# 06_USB_Interface.net
KiCad netlist of a schematic drawn in Altium Designer
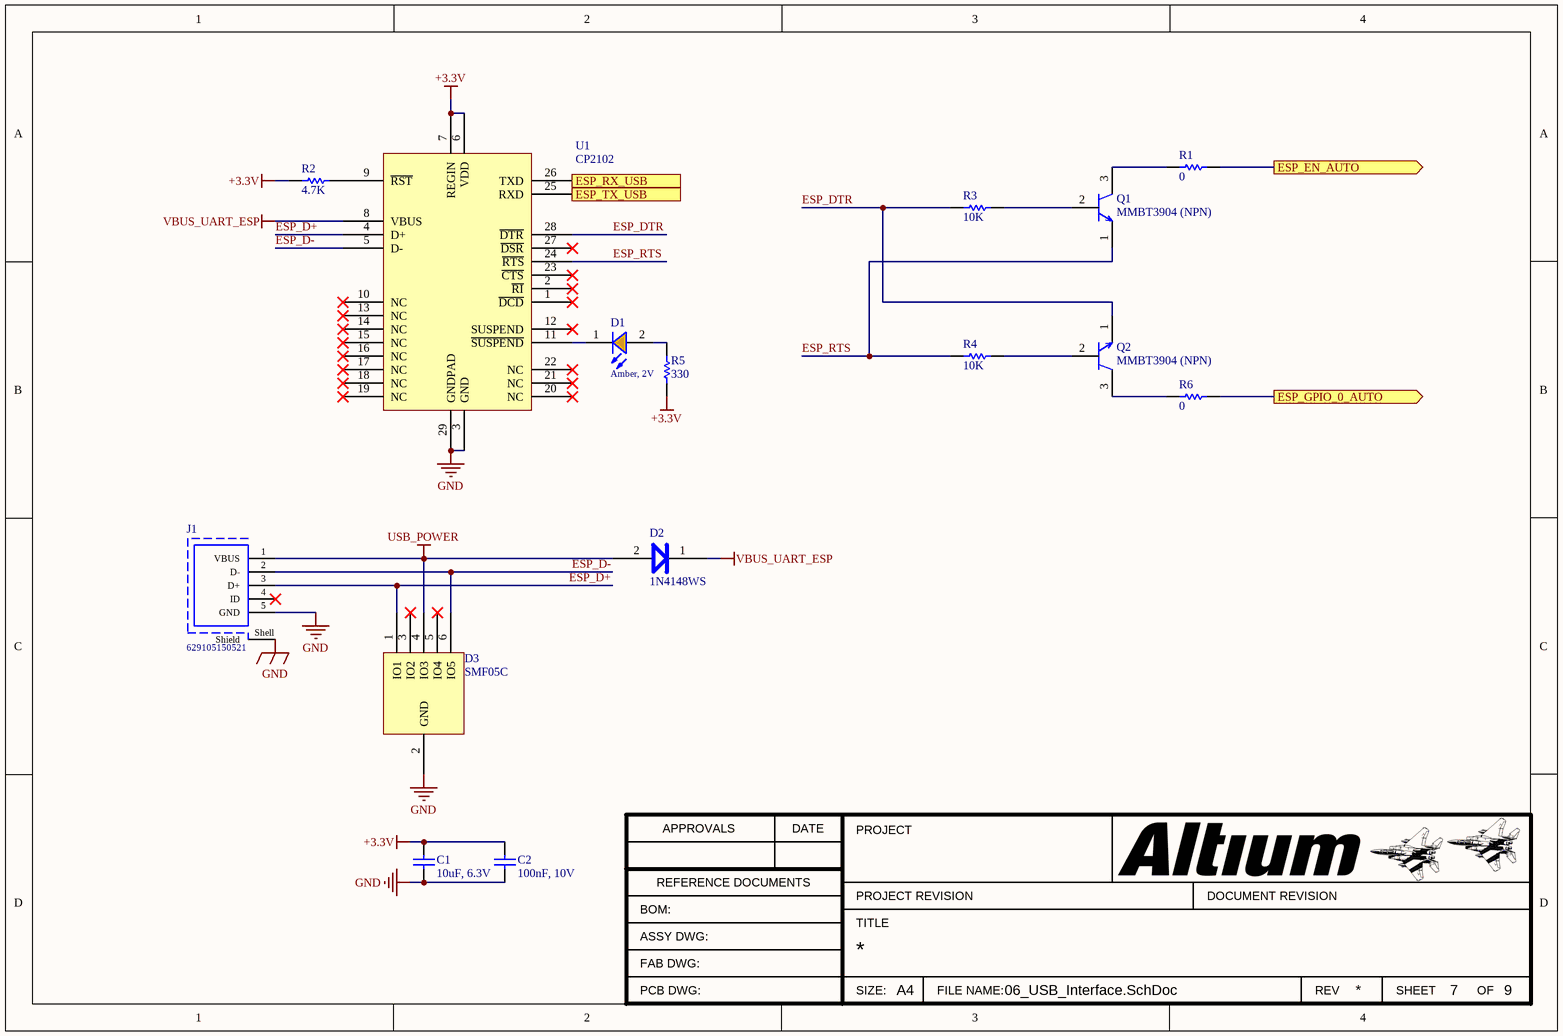
[diagram p0: 06_USB_Interface.SchDoc]

(export (version "E")
  (design (tool "Eeschema 10.0.6"))
  (components
    (comp (ref "C1")
      (value "10uF, 6.3V")
      (footprint "WCAP-CSGP_0603_H=0.8mm_Reflow")
      (description "WCAP-CSGP Multilayer Ceramic Chip Capacitor, General Purpose, size 0603, X5R, 10uF, 6.3V")
      (fields
        (field (name "MANUFACTURER PART NUMBER") "885012106006")
        (field (name "MANUFACTURER") "Wurth Elektronik")
      )
      (libsource (lib "Altium_WCAP-CSGP (rev20a)") (part "885012106006"))
    )
    (comp (ref "C2")
      (value "100nF, 10V")
      (footprint "WCAP-CSGP_0603_H=0.8mm_Reflow")
      (description "WCAP-CSGP Multilayer Ceramic Chip Capacitor, General Purpose, size 0603, X7R, 100nF, 10V")
      (fields
        (field (name "MANUFACTURER PART NUMBER") "885012206020")
        (field (name "MANUFACTURER") "Wurth Elektronik")
      )
      (libsource (lib "Altium_WCAP-CSGP (rev20a)") (part "885012206020"))
    )
    (comp (ref "D1")
      (value "Amber, 2V")
      (footprint "WL-SMCW_0603_H=0.7mm")
      (description "WL-SMCW SMT Mono-color Chip LED Waterclear, size 0603, Amber, 2V, 140deg")
      (fields (field (name "PART NUMBER") "150060AS75000") (field (name "PUBLISHER") "Wurth Elektronik"))
      (libsource (lib "Altium_WL-SMCW (rev20a)") (part "150060AS75000"))
    )
    (comp (ref "D2")
      (value "1N4148WS")
      (footprint "SODFL250X90-2N")
      (libsource (lib "MiclsLib") (part "1N4148WS"))
    )
    (comp (ref "D3")
      (value "SMF05C")
      (footprint "SOT65P210X110-6N")
      (libsource (lib "MiclsLib") (part "SMF05C"))
    )
    (comp (ref "J1")
      (value "629105150521")
      (footprint "629105150521")
      (description "Micro USB 2.0 Type B Receptacle WR-COM, Horizontal, SMT, with Pegs, High Current at Pin 1 & Pin 5")
      (fields (field (name "PUBLISHER") "Wurth Elektronik"))
      (libsource (lib "ALTIUM-WR-COM_USB_20-rev18d") (part "629105150521"))
    )
    (comp (ref "Q1")
      (value "MMBT3904 (NPN)")
      (footprint "SOT95P245X110-3N")
      (fields (field (name "MANUFACTURER") "On Semiconductor"))
      (libsource (lib "MiclsLib") (part "MMBT3904 (NPN)"))
    )
    (comp (ref "Q2")
      (value "MMBT3904 (NPN)")
      (footprint "SOT95P245X110-3N")
      (fields (field (name "MANUFACTURER") "On Semiconductor"))
      (libsource (lib "MiclsLib") (part "MMBT3904 (NPN)"))
    )
    (comp (ref "R1")
      (value "0")
      (footprint "RES-SM-0603")
      (description "Resistor")
      (fields (field (name "Comment") "RESISTOR SMD"))
      (libsource (lib "PIF_Library") (part "RESISTOR SMD"))
    )
    (comp (ref "R2")
      (value "4.7K")
      (footprint "RES-SM-0603")
      (description "Resistor")
      (fields (field (name "Comment") "RESISTOR SMD"))
      (libsource (lib "PIF_Library") (part "RESISTOR SMD"))
    )
    (comp (ref "R3")
      (value "10K")
      (footprint "RES-SM-0603")
      (description "Resistor")
      (fields (field (name "Comment") "RESISTOR SMD"))
      (libsource (lib "PIF_Library") (part "RESISTOR SMD"))
    )
    (comp (ref "R4")
      (value "10K")
      (footprint "RES-SM-0603")
      (description "Resistor")
      (fields (field (name "Comment") "RESISTOR SMD"))
      (libsource (lib "PIF_Library") (part "RESISTOR SMD"))
    )
    (comp (ref "R5")
      (value "330")
      (footprint "RES-SM-0603")
      (description "Resistor")
      (fields (field (name "Comment") "RESISTOR SMD"))
      (libsource (lib "PIF_Library") (part "RESISTOR SMD"))
    )
    (comp (ref "R6")
      (value "0")
      (footprint "RES-SM-0603")
      (description "Resistor")
      (fields (field (name "Comment") "RESISTOR SMD"))
      (libsource (lib "PIF_Library") (part "RESISTOR SMD"))
    )
    (comp (ref "U1")
      (value "CP2102")
      (footprint "QFN50P500X500X90_HS-29N")
      (libsource (lib "MiclsLib") (part "CP2102"))
    )
  )
  (nets
    (net (code "1") (name "+3.3V") (class "Default")
      (node (ref "C1") (pin "2") (pinfunction "2_2") (pintype "passive"))
      (node (ref "C2") (pin "2") (pinfunction "2_2") (pintype "passive"))
      (node (ref "R2") (pin "2") (pinfunction "2_2") (pintype "passive"))
      (node (ref "R5") (pin "2") (pinfunction "2_2") (pintype "passive"))
      (node (ref "U1") (pin "6") (pinfunction "VDD_6") (pintype "passive"))
      (node (ref "U1") (pin "7") (pinfunction "REGIN_7") (pintype "passive"))
    )
    (net (code "2") (name "/ESP_D+") (class "Default")
      (node (ref "D3") (pin "1") (pinfunction "IO1_1") (pintype "passive"))
      (node (ref "J1") (pin "3") (pinfunction "D+_3") (pintype "passive"))
      (node (ref "U1") (pin "4") (pinfunction "D+_4") (pintype "passive"))
    )
    (net (code "3") (name "/ESP_D-") (class "Default")
      (node (ref "D3") (pin "6") (pinfunction "IO5_6") (pintype "passive"))
      (node (ref "J1") (pin "2") (pinfunction "D-_2") (pintype "passive"))
      (node (ref "U1") (pin "5") (pinfunction "D-_5") (pintype "passive"))
    )
    (net (code "4") (name "/ESP_DTR") (class "Default")
      (node (ref "Q2") (pin "1") (pinfunction "1_1") (pintype "passive"))
      (node (ref "R3") (pin "1") (pinfunction "1_1") (pintype "passive"))
      (node (ref "U1") (pin "28") (pinfunction "~{DTR}_28") (pintype "passive"))
    )
    (net (code "5") (name "/ESP_EN_AUTO") (class "Default")
      (node (ref "R1") (pin "2") (pinfunction "2_2") (pintype "passive"))
    )
    (net (code "6") (name "/ESP_GPIO_0_AUTO") (class "Default")
      (node (ref "R6") (pin "2") (pinfunction "2_2") (pintype "passive"))
    )
    (net (code "7") (name "/ESP_RTS") (class "Default")
      (node (ref "Q1") (pin "1") (pinfunction "1_1") (pintype "passive"))
      (node (ref "R4") (pin "1") (pinfunction "1_1") (pintype "passive"))
      (node (ref "U1") (pin "24") (pinfunction "~{RTS}_24") (pintype "passive"))
    )
    (net (code "8") (name "/ESP_RX_USB") (class "Default")
      (node (ref "U1") (pin "26") (pinfunction "TXD_26") (pintype "passive"))
    )
    (net (code "9") (name "/ESP_TX_USB") (class "Default")
      (node (ref "U1") (pin "25") (pinfunction "RXD_25") (pintype "passive"))
    )
    (net (code "10") (name "GND") (class "Default")
      (node (ref "C1") (pin "1") (pinfunction "1_1") (pintype "passive"))
      (node (ref "C2") (pin "1") (pinfunction "1_1") (pintype "passive"))
      (node (ref "D3") (pin "2") (pinfunction "GND_2") (pintype "passive"))
      (node (ref "J1") (pin "5") (pinfunction "GND_5") (pintype "passive"))
      (node (ref "J1") (pin "Shell") (pinfunction "Shield_Shell") (pintype "passive"))
      (node (ref "U1") (pin "29") (pinfunction "GNDPAD_29") (pintype "passive"))
      (node (ref "U1") (pin "3") (pinfunction "GND_3") (pintype "passive"))
    )
    (net (code "11") (name "Net-(D1-A)") (class "Default")
      (node (ref "D1") (pin "2") (pinfunction "A_2") (pintype "passive"))
      (node (ref "R5") (pin "1") (pinfunction "1_1") (pintype "passive"))
    )
    (net (code "12") (name "Net-(D1-K)") (class "Default")
      (node (ref "D1") (pin "1") (pinfunction "K_1") (pintype "passive"))
      (node (ref "U1") (pin "11") (pinfunction "~{SUSPEND}_11") (pintype "passive"))
    )
    (net (code "13") (name "Net-(Q1-Pad2)") (class "Default")
      (node (ref "Q1") (pin "2") (pinfunction "2_2") (pintype "passive"))
      (node (ref "R3") (pin "2") (pinfunction "2_2") (pintype "passive"))
    )
    (net (code "14") (name "Net-(Q1-Pad3)") (class "Default")
      (node (ref "Q1") (pin "3") (pinfunction "3_3") (pintype "passive"))
      (node (ref "R1") (pin "1") (pinfunction "1_1") (pintype "passive"))
    )
    (net (code "15") (name "Net-(Q2-Pad2)") (class "Default")
      (node (ref "Q2") (pin "2") (pinfunction "2_2") (pintype "passive"))
      (node (ref "R4") (pin "2") (pinfunction "2_2") (pintype "passive"))
    )
    (net (code "16") (name "Net-(Q2-Pad3)") (class "Default")
      (node (ref "Q2") (pin "3") (pinfunction "3_3") (pintype "passive"))
      (node (ref "R6") (pin "1") (pinfunction "1_1") (pintype "passive"))
    )
    (net (code "17") (name "Net-(U1-~{RST})") (class "Default")
      (node (ref "R2") (pin "1") (pinfunction "1_1") (pintype "passive"))
      (node (ref "U1") (pin "9") (pinfunction "~{RST}_9") (pintype "passive"))
    )
    (net (code "18") (name "USB_POWER") (class "Default")
      (node (ref "D2") (pin "2") (pinfunction "2_2") (pintype "passive"))
      (node (ref "D3") (pin "4") (pinfunction "IO3_4") (pintype "passive"))
      (node (ref "J1") (pin "1") (pinfunction "VBUS_1") (pintype "passive"))
    )
    (net (code "19") (name "VBUS_UART_ESP") (class "Default")
      (node (ref "D2") (pin "1") (pinfunction "1_1") (pintype "passive"))
      (node (ref "U1") (pin "8") (pinfunction "VBUS_8") (pintype "passive"))
    )
    (net (code "20") (name "unconnected-(D3-IO2-Pad3)") (class "Default")
      (node (ref "D3") (pin "3") (pinfunction "IO2_3") (pintype "passive+no_connect"))
    )
    (net (code "21") (name "unconnected-(D3-IO4-Pad5)") (class "Default")
      (node (ref "D3") (pin "5") (pinfunction "IO4_5") (pintype "passive+no_connect"))
    )
    (net (code "22") (name "unconnected-(J1-ID-Pad4)") (class "Default")
      (node (ref "J1") (pin "4") (pinfunction "ID_4") (pintype "passive+no_connect"))
    )
    (net (code "23") (name "unconnected-(U1-NC-Pad10)") (class "Default")
      (node (ref "U1") (pin "10") (pinfunction "NC_10") (pintype "passive+no_connect"))
    )
    (net (code "24") (name "unconnected-(U1-NC-Pad13)") (class "Default")
      (node (ref "U1") (pin "13") (pinfunction "NC_13") (pintype "passive+no_connect"))
    )
    (net (code "25") (name "unconnected-(U1-NC-Pad14)") (class "Default")
      (node (ref "U1") (pin "14") (pinfunction "NC_14") (pintype "passive+no_connect"))
    )
    (net (code "26") (name "unconnected-(U1-NC-Pad15)") (class "Default")
      (node (ref "U1") (pin "15") (pinfunction "NC_15") (pintype "passive+no_connect"))
    )
    (net (code "27") (name "unconnected-(U1-NC-Pad16)") (class "Default")
      (node (ref "U1") (pin "16") (pinfunction "NC_16") (pintype "passive+no_connect"))
    )
    (net (code "28") (name "unconnected-(U1-NC-Pad17)") (class "Default")
      (node (ref "U1") (pin "17") (pinfunction "NC_17") (pintype "passive+no_connect"))
    )
    (net (code "29") (name "unconnected-(U1-NC-Pad18)") (class "Default")
      (node (ref "U1") (pin "18") (pinfunction "NC_18") (pintype "passive+no_connect"))
    )
    (net (code "30") (name "unconnected-(U1-NC-Pad19)") (class "Default")
      (node (ref "U1") (pin "19") (pinfunction "NC_19") (pintype "passive+no_connect"))
    )
    (net (code "31") (name "unconnected-(U1-NC-Pad20)") (class "Default")
      (node (ref "U1") (pin "20") (pinfunction "NC_20") (pintype "passive+no_connect"))
    )
    (net (code "32") (name "unconnected-(U1-NC-Pad21)") (class "Default")
      (node (ref "U1") (pin "21") (pinfunction "NC_21") (pintype "passive+no_connect"))
    )
    (net (code "33") (name "unconnected-(U1-NC-Pad22)") (class "Default")
      (node (ref "U1") (pin "22") (pinfunction "NC_22") (pintype "passive+no_connect"))
    )
    (net (code "34") (name "unconnected-(U1-SUSPEND-Pad12)") (class "Default")
      (node (ref "U1") (pin "12") (pinfunction "SUSPEND_12") (pintype "passive+no_connect"))
    )
    (net (code "35") (name "unconnected-(U1-~{CTS}-Pad23)") (class "Default")
      (node (ref "U1") (pin "23") (pinfunction "~{CTS}_23") (pintype "passive+no_connect"))
    )
    (net (code "36") (name "unconnected-(U1-~{DCD}-Pad1)") (class "Default")
      (node (ref "U1") (pin "1") (pinfunction "~{DCD}_1") (pintype "passive+no_connect"))
    )
    (net (code "37") (name "unconnected-(U1-~{DSR}-Pad27)") (class "Default")
      (node (ref "U1") (pin "27") (pinfunction "~{DSR}_27") (pintype "passive+no_connect"))
    )
    (net (code "38") (name "unconnected-(U1-~{RI}-Pad2)") (class "Default")
      (node (ref "U1") (pin "2") (pinfunction "~{RI}_2") (pintype "passive+no_connect"))
    )
  )
)
